# Voltage_Sensing.net
KiCad netlist of a schematic drawn in Altium Designer
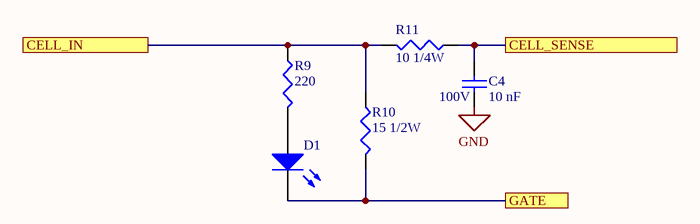
[diagram p0: Voltage Sensing.SchDoc]

(export (version "E")
  (design (tool "Eeschema 10.0.6"))
  (components
    (comp (ref "C4")
      (value "100V")
      (footprint "6-0805_N")
      (description "Capacitor")
      (fields (field (name "100V") "10 nF") (field (name "PUBLISHER") "Altium Limited"))
      (libsource (lib "Miscellaneous Devices") (part "Cap"))
    )
    (comp (ref "D1")
      (value "LED2")
      (footprint "DIOC1608X06N")
      (description "Green LED")
      (fields (field (name "PUBLISHER") "Altium Limited"))
      (libsource (lib "Miscellaneous Devices") (part "LED2"))
    )
    (comp (ref "R9")
      (value "220")
      (footprint "J1-0603")
      (description "Resistor")
      (fields (field (name "Comment") "Res3") (field (name "PUBLISHER") "Altium Limited"))
      (libsource (lib "Miscellaneous Devices") (part "Res3"))
    )
    (comp (ref "R10")
      (value "15 1/2W")
      (footprint "14-1210")
      (description "Resistor")
      (fields (field (name "Comment") "Res3") (field (name "PUBLISHER") "Altium Limited"))
      (libsource (lib "Miscellaneous Devices") (part "Res3"))
    )
    (comp (ref "R11")
      (value "10 1/4W")
      (footprint "C1206")
      (description "Resistor")
      (fields (field (name "PUBLISHER") "Altium Limited"))
      (libsource (lib "Miscellaneous Devices") (part "Res3"))
    )
  )
  (nets
    (net (code "1") (name "/CELL_IN") (class "Default")
      (node (ref "R10") (pin "1") (pinfunction "1_1") (pintype "passive"))
      (node (ref "R11") (pin "2") (pinfunction "2_2") (pintype "passive"))
      (node (ref "R9") (pin "1") (pinfunction "1_1") (pintype "passive"))
    )
    (net (code "2") (name "/CELL_SENSE") (class "Default")
      (node (ref "C4") (pin "2") (pinfunction "2_2") (pintype "passive"))
      (node (ref "R11") (pin "1") (pinfunction "1_1") (pintype "passive"))
    )
    (net (code "3") (name "/GATE") (class "Default")
      (node (ref "D1") (pin "2") (pinfunction "K_2") (pintype "passive"))
      (node (ref "R10") (pin "2") (pinfunction "2_2") (pintype "passive"))
    )
    (net (code "4") (name "GND") (class "Default")
      (node (ref "C4") (pin "1") (pinfunction "1_1") (pintype "passive"))
    )
    (net (code "5") (name "Net-(D1-A)") (class "Default")
      (node (ref "D1") (pin "1") (pinfunction "A_1") (pintype "passive"))
      (node (ref "R9") (pin "2") (pinfunction "2_2") (pintype "passive"))
    )
  )
)
